# TX.net
KiCad netlist of a schematic drawn in Altium Designer
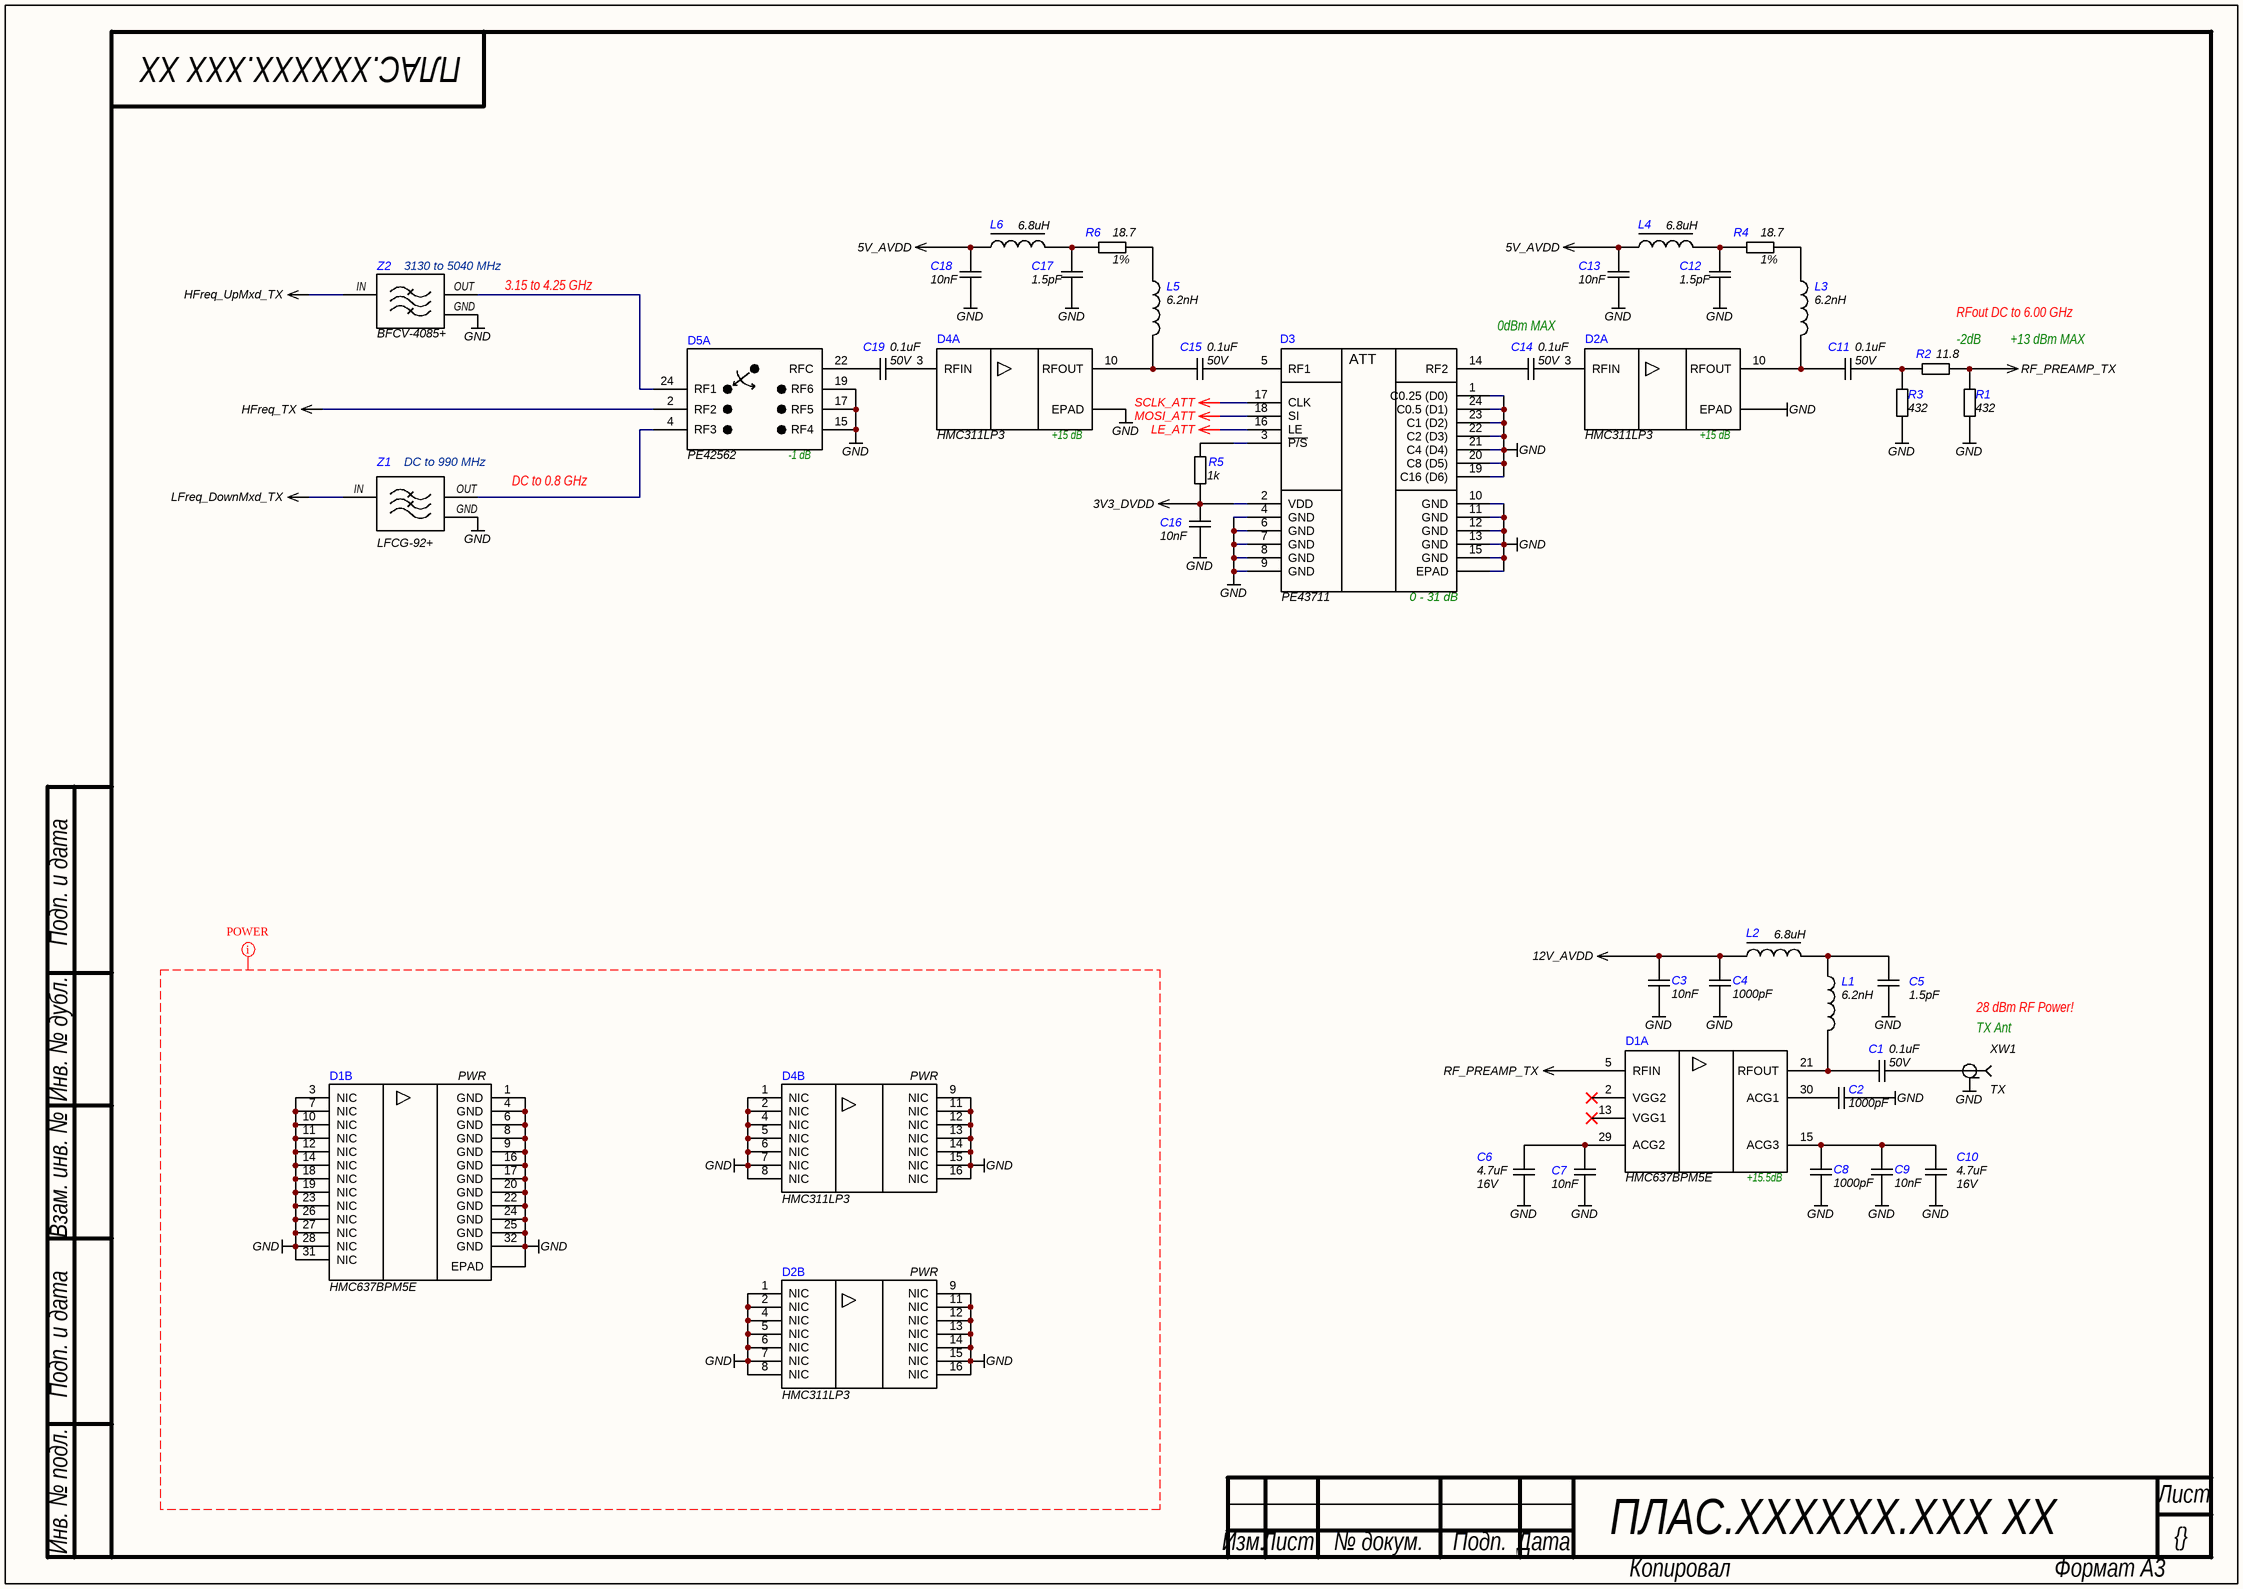
[diagram p0: TX.SchDoc]

(export (version "E")
  (design (tool "Eeschema 10.0.6"))
  (components
    (comp (ref "C1")
      (value "0.1uF")
      (footprint "C1206")
      (description "SMD Capacitor")
      (fields
        (field (name "MANUFACTURER") "Murata")
        (field (name "TOLERANCE") "5%")
        (field (name "VOLTAGE") "50V")
      )
      (libsource (lib "Kintex_SDR") (part "CAP"))
    )
    (comp (ref "C2")
      (value "1000pF")
      (footprint "C0402")
      (description "SMD Capacitor")
      (fields (field (name "MANUFACTURER") "Murata") (field (name "TOLERANCE") "5%"))
      (libsource (lib "Kintex_SDR") (part "CAP"))
    )
    (comp (ref "C3")
      (value "10nF")
      (footprint "C0402")
      (description "SMD Capacitor")
      (fields (field (name "MANUFACTURER") "Murata") (field (name "TOLERANCE") "10%"))
      (libsource (lib "Kintex_SDR") (part "CAP"))
    )
    (comp (ref "C4")
      (value "1000pF")
      (footprint "C0402")
      (description "SMD Capacitor")
      (fields (field (name "MANUFACTURER") "Murata") (field (name "TOLERANCE") "5%"))
      (libsource (lib "Kintex_SDR") (part "CAP"))
    )
    (comp (ref "C5")
      (value "1.5pF")
      (footprint "C0402")
      (description "SMD Capacitor")
      (fields (field (name "MANUFACTURER") "Murata") (field (name "TOLERANCE") "±0.05pF"))
      (libsource (lib "Kintex_SDR") (part "CAP"))
    )
    (comp (ref "C6")
      (value "4.7uF")
      (footprint "C0603")
      (description "SMD Capacitor")
      (fields
        (field (name "MANUFACTURER") "Samsung")
        (field (name "TOLERANCE") "10%")
        (field (name "VOLTAGE") "16V")
      )
      (libsource (lib "Kintex_SDR") (part "CAP"))
    )
    (comp (ref "C7")
      (value "10nF")
      (footprint "C0402")
      (description "SMD Capacitor")
      (fields (field (name "MANUFACTURER") "Murata") (field (name "TOLERANCE") "10%"))
      (libsource (lib "Kintex_SDR") (part "CAP"))
    )
    (comp (ref "C8")
      (value "1000pF")
      (footprint "C0402")
      (description "SMD Capacitor")
      (fields (field (name "MANUFACTURER") "Murata") (field (name "TOLERANCE") "5%"))
      (libsource (lib "Kintex_SDR") (part "CAP"))
    )
    (comp (ref "C9")
      (value "10nF")
      (footprint "C0402")
      (description "SMD Capacitor")
      (fields (field (name "MANUFACTURER") "Murata") (field (name "TOLERANCE") "10%"))
      (libsource (lib "Kintex_SDR") (part "CAP"))
    )
    (comp (ref "C10")
      (value "4.7uF")
      (footprint "C0603")
      (description "SMD Capacitor")
      (fields
        (field (name "MANUFACTURER") "Samsung")
        (field (name "TOLERANCE") "10%")
        (field (name "VOLTAGE") "16V")
      )
      (libsource (lib "Kintex_SDR") (part "CAP"))
    )
    (comp (ref "C11")
      (value "0.1uF")
      (footprint "C1206")
      (description "SMD Capacitor")
      (fields
        (field (name "MANUFACTURER") "Murata")
        (field (name "TOLERANCE") "5%")
        (field (name "VOLTAGE") "50V")
      )
      (libsource (lib "Kintex_SDR") (part "CAP"))
    )
    (comp (ref "C12")
      (value "1.5pF")
      (footprint "C0402")
      (description "SMD Capacitor")
      (fields (field (name "MANUFACTURER") "Murata") (field (name "TOLERANCE") "±0.05pF"))
      (libsource (lib "Kintex_SDR") (part "CAP"))
    )
    (comp (ref "C13")
      (value "10nF")
      (footprint "C0402")
      (description "SMD Capacitor")
      (fields (field (name "MANUFACTURER") "Murata") (field (name "TOLERANCE") "10%"))
      (libsource (lib "Kintex_SDR") (part "CAP"))
    )
    (comp (ref "C14")
      (value "0.1uF")
      (footprint "C1206")
      (description "SMD Capacitor")
      (fields
        (field (name "MANUFACTURER") "Murata")
        (field (name "TOLERANCE") "5%")
        (field (name "VOLTAGE") "50V")
      )
      (libsource (lib "Kintex_SDR") (part "CAP"))
    )
    (comp (ref "C15")
      (value "0.1uF")
      (footprint "C1206")
      (description "SMD Capacitor")
      (fields
        (field (name "MANUFACTURER") "Murata")
        (field (name "TOLERANCE") "5%")
        (field (name "VOLTAGE") "50V")
      )
      (libsource (lib "Kintex_SDR") (part "CAP"))
    )
    (comp (ref "C16")
      (value "10nF")
      (footprint "C0402")
      (description "SMD Capacitor")
      (fields (field (name "MANUFACTURER") "Murata") (field (name "TOLERANCE") "10%"))
      (libsource (lib "Kintex_SDR") (part "CAP"))
    )
    (comp (ref "C17")
      (value "1.5pF")
      (footprint "C0402")
      (description "SMD Capacitor")
      (fields (field (name "MANUFACTURER") "Murata") (field (name "TOLERANCE") "±0.05pF"))
      (libsource (lib "Kintex_SDR") (part "CAP"))
    )
    (comp (ref "C18")
      (value "10nF")
      (footprint "C0402")
      (description "SMD Capacitor")
      (fields (field (name "MANUFACTURER") "Murata") (field (name "TOLERANCE") "10%"))
      (libsource (lib "Kintex_SDR") (part "CAP"))
    )
    (comp (ref "C19")
      (value "0.1uF")
      (footprint "C1206")
      (description "SMD Capacitor")
      (fields
        (field (name "MANUFACTURER") "Murata")
        (field (name "TOLERANCE") "5%")
        (field (name "VOLTAGE") "50V")
      )
      (libsource (lib "Kintex_SDR") (part "CAP"))
    )
    (comp (ref "D1")
      (value "HMC637BPM5E")
      (footprint "DBLib:LFCSP-32")
      (description "1 W Power Amplifier")
      (fields
        (field (name "MANUFACTURER") "Analog Devices")
        (field (name "VOLTAGE") "12 V at 345 mA typical")
      )
      (libsource (lib "DBLib") (part "HMC637BPM5E"))
    )
    (comp (ref "D2")
      (value "HMC311LP3")
      (footprint "DBLib:QFN-16 v2")
      (description "InGaP HBT GAIN BLOCK")
      (fields (field (name "MANUFACTURER") "Analog Devices"))
      (libsource (lib "DBLib") (part "HMC311LP3"))
    )
    (comp (ref "D3")
      (value "PE43711")
      (footprint "QFN-24")
      (description "The PE43711 is a 50Ω, HaRP™ technology-enhanced, 7-bit RF digital step attenuator")
      (fields (field (name "MANUFACTURER") "Peregrine Technical Solutions"))
      (libsource (lib "DBLib") (part "PE43711"))
    )
    (comp (ref "D4")
      (value "HMC311LP3")
      (footprint "DBLib:QFN-16 v2")
      (description "InGaP HBT GAIN BLOCK")
      (fields (field (name "MANUFACTURER") "Analog Devices"))
      (libsource (lib "DBLib") (part "HMC311LP3"))
    )
    (comp (ref "D5")
      (value "PE42562")
      (footprint "QFN-24")
      (description "The PE42582 is a HaRP™ technology-enhanced absorptive SP6T RF switch")
      (fields (field (name "MANUFACTURER") "Peregrine Technical Solutions"))
      (libsource (lib "DBLib") (part "PE42562"))
    )
    (comp (ref "L1")
      (value "6.2nH")
      (footprint "DBLib:L0805_HP")
      (description "Chip SMD Inductor")
      (fields (field (name "MANUFACTURER") "Coilcraft") (field (name "TOLERANCE") "5%"))
      (libsource (lib "DBLib") (part "Inductor RF"))
    )
    (comp (ref "L2")
      (value "6.8uH")
      (footprint "DBLib:XFL3012")
      (description "Chip SMD Inductor")
      (fields (field (name "MANUFACTURER") "Coilcraft") (field (name "TOLERANCE") "±5%"))
      (libsource (lib "DBLib") (part "Inductor"))
    )
    (comp (ref "L3")
      (value "6.2nH")
      (footprint "DBLib:L0805_HP")
      (description "Chip SMD Inductor")
      (fields (field (name "MANUFACTURER") "Coilcraft") (field (name "TOLERANCE") "5%"))
      (libsource (lib "DBLib") (part "Inductor RF"))
    )
    (comp (ref "L4")
      (value "6.8uH")
      (footprint "DBLib:XFL3012")
      (description "Chip SMD Inductor")
      (fields (field (name "MANUFACTURER") "Coilcraft") (field (name "TOLERANCE") "±5%"))
      (libsource (lib "DBLib") (part "Inductor"))
    )
    (comp (ref "L5")
      (value "6.2nH")
      (footprint "DBLib:L0805_HP")
      (description "Chip SMD Inductor")
      (fields (field (name "MANUFACTURER") "Coilcraft") (field (name "TOLERANCE") "5%"))
      (libsource (lib "DBLib") (part "Inductor RF"))
    )
    (comp (ref "L6")
      (value "6.8uH")
      (footprint "DBLib:XFL3012")
      (description "Chip SMD Inductor")
      (fields (field (name "MANUFACTURER") "Coilcraft") (field (name "TOLERANCE") "±5%"))
      (libsource (lib "DBLib") (part "Inductor"))
    )
    (comp (ref "R1")
      (value "432")
      (footprint "R0402")
      (description "SMD Resistor")
      (fields (field (name "POWER") "0.1 Wt") (field (name "TOLERANCE") "±1%"))
      (libsource (lib "") (part "RES_1"))
    )
    (comp (ref "R2")
      (value "11.8")
      (footprint "R0402")
      (description "SMD Resistor")
      (fields (field (name "POWER") "0.063 Wt") (field (name "TOLERANCE") "±1%"))
      (libsource (lib "Kintex_SDR") (part "RES"))
    )
    (comp (ref "R3")
      (value "432")
      (footprint "R0402")
      (description "SMD Resistor")
      (fields (field (name "POWER") "0.1 Wt") (field (name "TOLERANCE") "±1%"))
      (libsource (lib "") (part "RES_1"))
    )
    (comp (ref "R4")
      (value "18.7")
      (footprint "R0805")
      (description "SMD Resistor")
      (fields
        (field (name "POWER") "0.125 Wt")
        (field (name "TOLERANCE") "1%")
        (field (name "MANUFACTURER") "Panasonic Electronic Components")
      )
      (libsource (lib "Kintex_SDR") (part "RES"))
    )
    (comp (ref "R5")
      (value "1k")
      (footprint "R0402")
      (description "SMD Resistor")
      (fields (field (name "POWER") "0.062 Wt") (field (name "TOLERANCE") "5%"))
      (libsource (lib "") (part "RES_2"))
    )
    (comp (ref "R6")
      (value "18.7")
      (footprint "R0805")
      (description "SMD Resistor")
      (fields
        (field (name "POWER") "0.125 Wt")
        (field (name "TOLERANCE") "1%")
        (field (name "MANUFACTURER") "Panasonic Electronic Components")
      )
      (libsource (lib "Kintex_SDR") (part "RES"))
    )
    (comp (ref "XW1")
      (value "TX")
      (footprint "MOLEX SD-73251-135 (Gold)")
      (description "50 Ohms, SMA Jack, Vertica")
      (fields (field (name "MANUFACTURER") "Molex"))
      (libsource (lib "DBLib") (part "RF Connector"))
    )
    (comp (ref "Z1")
      (value "LFCG-92+")
      (footprint "GE0805C-2")
      (description "Low Pass Filter")
      (fields (field (name "MANUFACTURER") "Mini-Circuits") (field (name "FREQUENCY") "DC to 990 MHz"))
      (libsource (lib "DBLib") (part "LFCG-92+"))
    )
    (comp (ref "Z2")
      (value "BFCV-4085+")
      (footprint "JV1210C")
      (description "Bandpass Filter")
      (fields (field (name "MANUFACTURER") "Mini-Circuits") (field (name "FREQUENCY") "3130 to 5040 MHz"))
      (libsource (lib "DBLib") (part "BFCV-4085+"))
    )
  )
  (nets
    (net (code "1") (name "3V3_DVDD") (class "Default")
      (node (ref "C16") (pin "2") (pinfunction "2_2") (pintype "passive"))
      (node (ref "D3") (pin "2") (pinfunction "VDD_2") (pintype "passive"))
      (node (ref "R5") (pin "1") (pinfunction "1_1") (pintype "passive"))
    )
    (net (code "2") (name "5V_AVDD") (class "Default")
      (node (ref "C13") (pin "2") (pinfunction "2_2") (pintype "passive"))
      (node (ref "C18") (pin "2") (pinfunction "2_2") (pintype "passive"))
      (node (ref "L4") (pin "1") (pinfunction "1_1") (pintype "passive"))
      (node (ref "L6") (pin "1") (pinfunction "1_1") (pintype "passive"))
    )
    (net (code "3") (name "12V_AVDD") (class "Default")
      (node (ref "C3") (pin "2") (pinfunction "2_2") (pintype "passive"))
      (node (ref "C4") (pin "2") (pinfunction "2_2") (pintype "passive"))
      (node (ref "L2") (pin "1") (pinfunction "1_1") (pintype "passive"))
    )
    (net (code "4") (name "GND") (class "Default")
      (node (ref "C10") (pin "2") (pinfunction "2_2") (pintype "passive"))
      (node (ref "C12") (pin "1") (pinfunction "1_1") (pintype "passive"))
      (node (ref "C13") (pin "1") (pinfunction "1_1") (pintype "passive"))
      (node (ref "C16") (pin "1") (pinfunction "1_1") (pintype "passive"))
      (node (ref "C17") (pin "1") (pinfunction "1_1") (pintype "passive"))
      (node (ref "C18") (pin "1") (pinfunction "1_1") (pintype "passive"))
      (node (ref "C2") (pin "2") (pinfunction "2_2") (pintype "passive"))
      (node (ref "C3") (pin "1") (pinfunction "1_1") (pintype "passive"))
      (node (ref "C4") (pin "1") (pinfunction "1_1") (pintype "passive"))
      (node (ref "C5") (pin "1") (pinfunction "1_1") (pintype "passive"))
      (node (ref "C6") (pin "2") (pinfunction "2_2") (pintype "passive"))
      (node (ref "C7") (pin "1") (pinfunction "1_1") (pintype "passive"))
      (node (ref "C8") (pin "1") (pinfunction "1_1") (pintype "passive"))
      (node (ref "C9") (pin "1") (pinfunction "1_1") (pintype "passive"))
      (node (ref "D1") (pin "0") (pinfunction "EPAD_0") (pintype "passive"))
      (node (ref "D1") (pin "1") (pinfunction "GND_1") (pintype "passive"))
      (node (ref "D1") (pin "10") (pinfunction "NIC_10") (pintype "passive"))
      (node (ref "D1") (pin "11") (pinfunction "NIC_11") (pintype "passive"))
      (node (ref "D1") (pin "12") (pinfunction "NIC_12") (pintype "passive"))
      (node (ref "D1") (pin "14") (pinfunction "NIC_14") (pintype "passive"))
      (node (ref "D1") (pin "16") (pinfunction "GND_16") (pintype "passive"))
      (node (ref "D1") (pin "17") (pinfunction "GND_17") (pintype "passive"))
      (node (ref "D1") (pin "18") (pinfunction "NIC_18") (pintype "passive"))
      (node (ref "D1") (pin "19") (pinfunction "NIC_19") (pintype "passive"))
      (node (ref "D1") (pin "20") (pinfunction "GND_20") (pintype "passive"))
      (node (ref "D1") (pin "22") (pinfunction "GND_22") (pintype "passive"))
      (node (ref "D1") (pin "23") (pinfunction "NIC_23") (pintype "passive"))
      (node (ref "D1") (pin "24") (pinfunction "GND_24") (pintype "passive"))
      (node (ref "D1") (pin "25") (pinfunction "GND_25") (pintype "passive"))
      (node (ref "D1") (pin "26") (pinfunction "NIC_26") (pintype "passive"))
      (node (ref "D1") (pin "27") (pinfunction "NIC_27") (pintype "passive"))
      (node (ref "D1") (pin "28") (pinfunction "NIC_28") (pintype "passive"))
      (node (ref "D1") (pin "3") (pinfunction "NIC_3") (pintype "passive"))
      (node (ref "D1") (pin "31") (pinfunction "NIC_31") (pintype "passive"))
      (node (ref "D1") (pin "32") (pinfunction "GND_32") (pintype "passive"))
      (node (ref "D1") (pin "4") (pinfunction "GND_4") (pintype "passive"))
      (node (ref "D1") (pin "6") (pinfunction "GND_6") (pintype "passive"))
      (node (ref "D1") (pin "7") (pinfunction "NIC_7") (pintype "passive"))
      (node (ref "D1") (pin "8") (pinfunction "GND_8") (pintype "passive"))
      (node (ref "D1") (pin "9") (pinfunction "GND_9") (pintype "passive"))
      (node (ref "D2") (pin "1") (pinfunction "NIC_1") (pintype "passive"))
      (node (ref "D2") (pin "11") (pinfunction "NIC_11") (pintype "passive"))
      (node (ref "D2") (pin "12") (pinfunction "NIC_12") (pintype "passive"))
      (node (ref "D2") (pin "13") (pinfunction "NIC_13") (pintype "passive"))
      (node (ref "D2") (pin "14") (pinfunction "NIC_14") (pintype "passive"))
      (node (ref "D2") (pin "15") (pinfunction "NIC_15") (pintype "passive"))
      (node (ref "D2") (pin "16") (pinfunction "NIC_16") (pintype "passive"))
      (node (ref "D2") (pin "17") (pinfunction "EPAD_17") (pintype "passive"))
      (node (ref "D2") (pin "2") (pinfunction "NIC_2") (pintype "passive"))
      (node (ref "D2") (pin "4") (pinfunction "NIC_4") (pintype "passive"))
      (node (ref "D2") (pin "5") (pinfunction "NIC_5") (pintype "passive"))
      (node (ref "D2") (pin "6") (pinfunction "NIC_6") (pintype "passive"))
      (node (ref "D2") (pin "7") (pinfunction "NIC_7") (pintype "passive"))
      (node (ref "D2") (pin "8") (pinfunction "NIC_8") (pintype "passive"))
      (node (ref "D2") (pin "9") (pinfunction "NIC_9") (pintype "passive"))
      (node (ref "D3") (pin "1") (pinfunction "C0.25_(D0)_1") (pintype "passive"))
      (node (ref "D3") (pin "10") (pinfunction "GND_10") (pintype "passive"))
      (node (ref "D3") (pin "11") (pinfunction "GND_11") (pintype "passive"))
      (node (ref "D3") (pin "12") (pinfunction "GND_12") (pintype "passive"))
      (node (ref "D3") (pin "13") (pinfunction "GND_13") (pintype "passive"))
      (node (ref "D3") (pin "15") (pinfunction "GND_15") (pintype "passive"))
      (node (ref "D3") (pin "19") (pinfunction "C16_(D6)_19") (pintype "passive"))
      (node (ref "D3") (pin "20") (pinfunction "C8_(D5)_20") (pintype "passive"))
      (node (ref "D3") (pin "21") (pinfunction "C4_(D4)_21") (pintype "passive"))
      (node (ref "D3") (pin "22") (pinfunction "C2_(D3)_22") (pintype "passive"))
      (node (ref "D3") (pin "23") (pinfunction "C1_(D2)_23") (pintype "passive"))
      (node (ref "D3") (pin "24") (pinfunction "C0.5_(D1)_24") (pintype "passive"))
      (node (ref "D3") (pin "25") (pinfunction "EPAD_25") (pintype "passive"))
      (node (ref "D3") (pin "4") (pinfunction "GND_4") (pintype "passive"))
      (node (ref "D3") (pin "6") (pinfunction "GND_6") (pintype "passive"))
      (node (ref "D3") (pin "7") (pinfunction "GND_7") (pintype "passive"))
      (node (ref "D3") (pin "8") (pinfunction "GND_8") (pintype "passive"))
      (node (ref "D3") (pin "9") (pinfunction "GND_9") (pintype "passive"))
      (node (ref "D4") (pin "1") (pinfunction "NIC_1") (pintype "passive"))
      (node (ref "D4") (pin "11") (pinfunction "NIC_11") (pintype "passive"))
      (node (ref "D4") (pin "12") (pinfunction "NIC_12") (pintype "passive"))
      (node (ref "D4") (pin "13") (pinfunction "NIC_13") (pintype "passive"))
      (node (ref "D4") (pin "14") (pinfunction "NIC_14") (pintype "passive"))
      (node (ref "D4") (pin "15") (pinfunction "NIC_15") (pintype "passive"))
      (node (ref "D4") (pin "16") (pinfunction "NIC_16") (pintype "passive"))
      (node (ref "D4") (pin "17") (pinfunction "EPAD_17") (pintype "passive"))
      (node (ref "D4") (pin "2") (pinfunction "NIC_2") (pintype "passive"))
      (node (ref "D4") (pin "4") (pinfunction "NIC_4") (pintype "passive"))
      (node (ref "D4") (pin "5") (pinfunction "NIC_5") (pintype "passive"))
      (node (ref "D4") (pin "6") (pinfunction "NIC_6") (pintype "passive"))
      (node (ref "D4") (pin "7") (pinfunction "NIC_7") (pintype "passive"))
      (node (ref "D4") (pin "8") (pinfunction "NIC_8") (pintype "passive"))
      (node (ref "D4") (pin "9") (pinfunction "NIC_9") (pintype "passive"))
      (node (ref "D5") (pin "15") (pinfunction "RF4_15") (pintype "passive"))
      (node (ref "D5") (pin "17") (pinfunction "RF5_17") (pintype "passive"))
      (node (ref "D5") (pin "19") (pinfunction "RF6_19") (pintype "passive"))
      (node (ref "R1") (pin "2") (pinfunction "2_2") (pintype "passive"))
      (node (ref "R3") (pin "2") (pinfunction "2_2") (pintype "passive"))
      (node (ref "XW1") (pin "G") (pinfunction "GND_G") (pintype "passive"))
      (node (ref "Z1") (pin "GND") (pinfunction "GND_GND") (pintype "passive"))
      (node (ref "Z2") (pin "GND") (pinfunction "GND_GND") (pintype "passive"))
    )
    (net (code "5") (name "HFreq_TX") (class "Default")
      (node (ref "D5") (pin "2") (pinfunction "RF2_2") (pintype "passive"))
    )
    (net (code "6") (name "HFreq_UpMxd_TX") (class "Default")
      (node (ref "Z2") (pin "IN") (pinfunction "IN_IN") (pintype "passive"))
    )
    (net (code "7") (name "LE_ATT") (class "Default")
      (node (ref "D3") (pin "16") (pinfunction "LE_16") (pintype "passive"))
    )
    (net (code "8") (name "LFreq_DownMxd_TX") (class "Default")
      (node (ref "Z1") (pin "IN") (pinfunction "IN_IN") (pintype "passive"))
    )
    (net (code "9") (name "MOSI_ATT") (class "Default")
      (node (ref "D3") (pin "18") (pinfunction "SI_18") (pintype "passive"))
    )
    (net (code "10") (name "Net-(C5-Pad2)") (class "Default")
      (node (ref "C5") (pin "2") (pinfunction "2_2") (pintype "passive"))
      (node (ref "L1") (pin "2") (pinfunction "2_2") (pintype "passive"))
      (node (ref "L2") (pin "2") (pinfunction "2_2") (pintype "passive"))
    )
    (net (code "11") (name "Net-(C11-Pad1)") (class "Default")
      (node (ref "C11") (pin "1") (pinfunction "1_1") (pintype "passive"))
      (node (ref "R2") (pin "2") (pinfunction "2_2") (pintype "passive"))
      (node (ref "R3") (pin "1") (pinfunction "1_1") (pintype "passive"))
    )
    (net (code "12") (name "Net-(C12-Pad2)") (class "Default")
      (node (ref "C12") (pin "2") (pinfunction "2_2") (pintype "passive"))
      (node (ref "L4") (pin "2") (pinfunction "2_2") (pintype "passive"))
      (node (ref "R4") (pin "2") (pinfunction "2_2") (pintype "passive"))
    )
    (net (code "13") (name "Net-(C17-Pad2)") (class "Default")
      (node (ref "C17") (pin "2") (pinfunction "2_2") (pintype "passive"))
      (node (ref "L6") (pin "2") (pinfunction "2_2") (pintype "passive"))
      (node (ref "R6") (pin "2") (pinfunction "2_2") (pintype "passive"))
    )
    (net (code "14") (name "Net-(D1A-ACG1)") (class "Default")
      (node (ref "C2") (pin "1") (pinfunction "1_1") (pintype "passive"))
      (node (ref "D1") (pin "30") (pinfunction "ACG1_30") (pintype "passive"))
    )
    (net (code "15") (name "Net-(D1A-ACG2)") (class "Default")
      (node (ref "C6") (pin "1") (pinfunction "1_1") (pintype "passive"))
      (node (ref "C7") (pin "2") (pinfunction "2_2") (pintype "passive"))
      (node (ref "D1") (pin "29") (pinfunction "ACG2_29") (pintype "passive"))
    )
    (net (code "16") (name "Net-(D1A-ACG3)") (class "Default")
      (node (ref "C10") (pin "1") (pinfunction "1_1") (pintype "passive"))
      (node (ref "C8") (pin "2") (pinfunction "2_2") (pintype "passive"))
      (node (ref "C9") (pin "2") (pinfunction "2_2") (pintype "passive"))
      (node (ref "D1") (pin "15") (pinfunction "ACG3_15") (pintype "passive"))
    )
    (net (code "17") (name "Net-(D1A-RFOUT)") (class "Default")
      (node (ref "C1") (pin "2") (pinfunction "2_2") (pintype "passive"))
      (node (ref "D1") (pin "21") (pinfunction "RFOUT_21") (pintype "passive"))
      (node (ref "L1") (pin "1") (pinfunction "1_1") (pintype "passive"))
    )
    (net (code "18") (name "Net-(D2A-RFIN)") (class "Default")
      (node (ref "C14") (pin "1") (pinfunction "1_1") (pintype "passive"))
      (node (ref "D2") (pin "3") (pinfunction "RFIN_3") (pintype "passive"))
    )
    (net (code "19") (name "Net-(D2A-RFOUT)") (class "Default")
      (node (ref "C11") (pin "2") (pinfunction "2_2") (pintype "passive"))
      (node (ref "D2") (pin "10") (pinfunction "RFOUT_10") (pintype "passive"))
      (node (ref "L3") (pin "1") (pinfunction "1_1") (pintype "passive"))
    )
    (net (code "20") (name "Net-(D3-RF1)") (class "Default")
      (node (ref "C15") (pin "1") (pinfunction "1_1") (pintype "passive"))
      (node (ref "D3") (pin "5") (pinfunction "RF1_5") (pintype "passive"))
    )
    (net (code "21") (name "Net-(D3-RF2)") (class "Default")
      (node (ref "C14") (pin "2") (pinfunction "2_2") (pintype "passive"))
      (node (ref "D3") (pin "14") (pinfunction "RF2_14") (pintype "passive"))
    )
    (net (code "22") (name "Net-(D3-~{P{slash}S})") (class "Default")
      (node (ref "D3") (pin "3") (pinfunction "~{P/S}_3") (pintype "passive"))
      (node (ref "R5") (pin "2") (pinfunction "2_2") (pintype "passive"))
    )
    (net (code "23") (name "Net-(D4A-RFIN)") (class "Default")
      (node (ref "C19") (pin "1") (pinfunction "1_1") (pintype "passive"))
      (node (ref "D4") (pin "3") (pinfunction "RFIN_3") (pintype "passive"))
    )
    (net (code "24") (name "Net-(D4A-RFOUT)") (class "Default")
      (node (ref "C15") (pin "2") (pinfunction "2_2") (pintype "passive"))
      (node (ref "D4") (pin "10") (pinfunction "RFOUT_10") (pintype "passive"))
      (node (ref "L5") (pin "1") (pinfunction "1_1") (pintype "passive"))
    )
    (net (code "25") (name "Net-(D5A-RF1)") (class "Default")
      (node (ref "D5") (pin "24") (pinfunction "RF1_24") (pintype "passive"))
      (node (ref "Z2") (pin "OUT") (pinfunction "OUT_OUT") (pintype "passive"))
    )
    (net (code "26") (name "Net-(D5A-RF3)") (class "Default")
      (node (ref "D5") (pin "4") (pinfunction "RF3_4") (pintype "passive"))
      (node (ref "Z1") (pin "OUT") (pinfunction "OUT_OUT") (pintype "passive"))
    )
    (net (code "27") (name "Net-(D5A-RFC)") (class "Default")
      (node (ref "C19") (pin "2") (pinfunction "2_2") (pintype "passive"))
      (node (ref "D5") (pin "22") (pinfunction "RFC_22") (pintype "passive"))
    )
    (net (code "28") (name "Net-(L3-Pad2)") (class "Default")
      (node (ref "L3") (pin "2") (pinfunction "2_2") (pintype "passive"))
      (node (ref "R4") (pin "1") (pinfunction "1_1") (pintype "passive"))
    )
    (net (code "29") (name "Net-(L5-Pad2)") (class "Default")
      (node (ref "L5") (pin "2") (pinfunction "2_2") (pintype "passive"))
      (node (ref "R6") (pin "1") (pinfunction "1_1") (pintype "passive"))
    )
    (net (code "30") (name "Net-(XW1-RF)") (class "Default")
      (node (ref "C1") (pin "1") (pinfunction "1_1") (pintype "passive"))
      (node (ref "XW1") (pin "S") (pinfunction "RF_S") (pintype "passive"))
    )
    (net (code "31") (name "RF_PREAMP_TX") (class "Default")
      (node (ref "D1") (pin "5") (pinfunction "RFIN_5") (pintype "passive"))
      (node (ref "R1") (pin "1") (pinfunction "1_1") (pintype "passive"))
      (node (ref "R2") (pin "1") (pinfunction "1_1") (pintype "passive"))
    )
    (net (code "32") (name "SCLK_ATT") (class "Default")
      (node (ref "D3") (pin "17") (pinfunction "CLK_17") (pintype "passive"))
    )
    (net (code "33") (name "unconnected-(D1A-VGG1-Pad13)") (class "Default")
      (node (ref "D1") (pin "13") (pinfunction "VGG1_13") (pintype "passive+no_connect"))
    )
    (net (code "34") (name "unconnected-(D1A-VGG2-Pad2)") (class "Default")
      (node (ref "D1") (pin "2") (pinfunction "VGG2_2") (pintype "passive+no_connect"))
    )
  )
)
